# Sheet3.net
KiCad netlist of a schematic drawn in Altium Designer
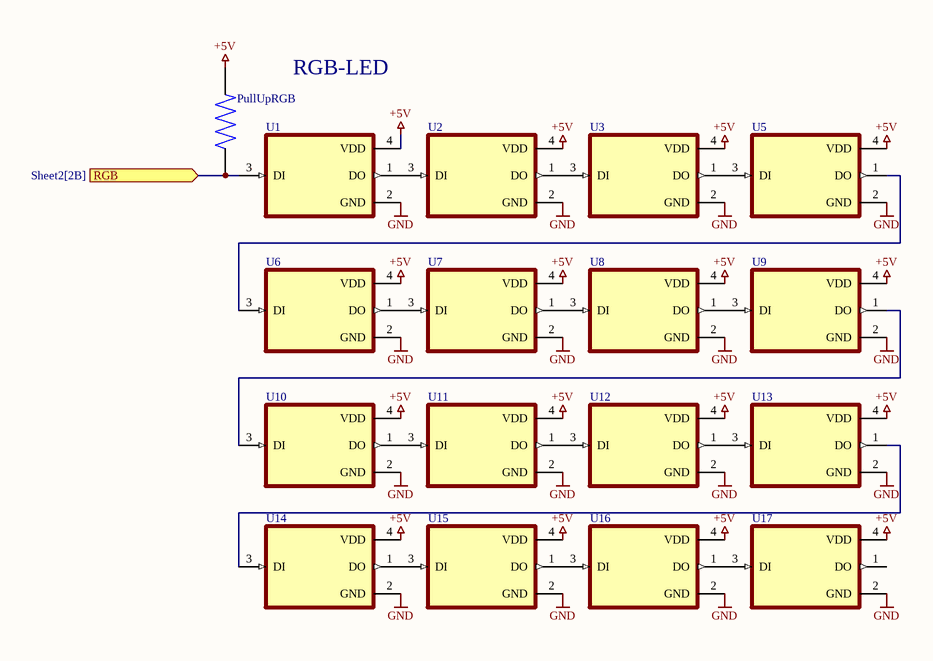
[diagram p0: Sheet3.SchDoc]

(export (version "E")
  (design (tool "Eeschema 10.0.6"))
  (components
    (comp (ref "PullUpRGB")
      (value "CRG0402F4K7")
      (footprint "CRG0402F4K7:RESC1005X40N")
      (fields (field (name "MF") "TE Connectivity") (field (name "TOLERANCE") "1%"))
      (libsource (lib "*") (part "CRG0402F4K7"))
    )
    (comp (ref "U1")
      (value "WS2812-2020")
      (footprint "WS2812_2020:LED_WS2812-2020")
      (description "Intelligent control LED light source, SMD-4")
      (fields (field (name "MF") "Worldsemi"))
      (libsource (lib "*") (part "WS2812-2020"))
    )
    (comp (ref "U2")
      (value "WS2812-2020")
      (footprint "WS2812_2020:LED_WS2812-2020")
      (description "Intelligent control LED light source, SMD-4")
      (fields (field (name "MF") "Worldsemi"))
      (libsource (lib "*") (part "WS2812-2020"))
    )
    (comp (ref "U3")
      (value "WS2812-2020")
      (footprint "WS2812_2020:LED_WS2812-2020")
      (description "Intelligent control LED light source, SMD-4")
      (fields (field (name "MF") "Worldsemi"))
      (libsource (lib "*") (part "WS2812-2020"))
    )
    (comp (ref "U5")
      (value "WS2812-2020")
      (footprint "WS2812_2020:LED_WS2812-2020")
      (description "Intelligent control LED light source, SMD-4")
      (fields (field (name "MF") "Worldsemi"))
      (libsource (lib "*") (part "WS2812-2020"))
    )
    (comp (ref "U6")
      (value "WS2812-2020")
      (footprint "WS2812_2020:LED_WS2812-2020")
      (description "Intelligent control LED light source, SMD-4")
      (fields (field (name "MF") "Worldsemi"))
      (libsource (lib "*") (part "WS2812-2020"))
    )
    (comp (ref "U7")
      (value "WS2812-2020")
      (footprint "WS2812_2020:LED_WS2812-2020")
      (description "Intelligent control LED light source, SMD-4")
      (fields (field (name "MF") "Worldsemi"))
      (libsource (lib "*") (part "WS2812-2020"))
    )
    (comp (ref "U8")
      (value "WS2812-2020")
      (footprint "WS2812_2020:LED_WS2812-2020")
      (description "Intelligent control LED light source, SMD-4")
      (fields (field (name "MF") "Worldsemi"))
      (libsource (lib "*") (part "WS2812-2020"))
    )
    (comp (ref "U9")
      (value "WS2812-2020")
      (footprint "WS2812_2020:LED_WS2812-2020")
      (description "Intelligent control LED light source, SMD-4")
      (fields (field (name "MF") "Worldsemi"))
      (libsource (lib "*") (part "WS2812-2020"))
    )
    (comp (ref "U10")
      (value "WS2812-2020")
      (footprint "WS2812_2020:LED_WS2812-2020")
      (description "Intelligent control LED light source, SMD-4")
      (fields (field (name "MF") "Worldsemi"))
      (libsource (lib "*") (part "WS2812-2020"))
    )
    (comp (ref "U11")
      (value "WS2812-2020")
      (footprint "WS2812_2020:LED_WS2812-2020")
      (description "Intelligent control LED light source, SMD-4")
      (fields (field (name "MF") "Worldsemi"))
      (libsource (lib "*") (part "WS2812-2020"))
    )
    (comp (ref "U12")
      (value "WS2812-2020")
      (footprint "WS2812_2020:LED_WS2812-2020")
      (description "Intelligent control LED light source, SMD-4")
      (fields (field (name "MF") "Worldsemi"))
      (libsource (lib "*") (part "WS2812-2020"))
    )
    (comp (ref "U13")
      (value "WS2812-2020")
      (footprint "WS2812_2020:LED_WS2812-2020")
      (description "Intelligent control LED light source, SMD-4")
      (fields (field (name "MF") "Worldsemi"))
      (libsource (lib "*") (part "WS2812-2020"))
    )
    (comp (ref "U14")
      (value "WS2812-2020")
      (footprint "WS2812_2020:LED_WS2812-2020")
      (description "Intelligent control LED light source, SMD-4")
      (fields (field (name "MF") "Worldsemi"))
      (libsource (lib "*") (part "WS2812-2020"))
    )
    (comp (ref "U15")
      (value "WS2812-2020")
      (footprint "WS2812_2020:LED_WS2812-2020")
      (description "Intelligent control LED light source, SMD-4")
      (fields (field (name "MF") "Worldsemi"))
      (libsource (lib "*") (part "WS2812-2020"))
    )
    (comp (ref "U16")
      (value "WS2812-2020")
      (footprint "WS2812_2020:LED_WS2812-2020")
      (description "Intelligent control LED light source, SMD-4")
      (fields (field (name "MF") "Worldsemi"))
      (libsource (lib "*") (part "WS2812-2020"))
    )
    (comp (ref "U17")
      (value "WS2812-2020")
      (footprint "WS2812_2020:LED_WS2812-2020")
      (description "Intelligent control LED light source, SMD-4")
      (fields (field (name "MF") "Worldsemi"))
      (libsource (lib "*") (part "WS2812-2020"))
    )
  )
  (nets
    (net (code "1") (name "+5V") (class "Default")
      (node (ref "PullUpRGB") (pin "2") (pinfunction "2_2") (pintype "passive"))
      (node (ref "U1") (pin "4") (pinfunction "VDD_4") (pintype "power_in"))
      (node (ref "U10") (pin "4") (pinfunction "VDD_4") (pintype "power_in"))
      (node (ref "U11") (pin "4") (pinfunction "VDD_4") (pintype "power_in"))
      (node (ref "U12") (pin "4") (pinfunction "VDD_4") (pintype "power_in"))
      (node (ref "U13") (pin "4") (pinfunction "VDD_4") (pintype "power_in"))
      (node (ref "U14") (pin "4") (pinfunction "VDD_4") (pintype "power_in"))
      (node (ref "U15") (pin "4") (pinfunction "VDD_4") (pintype "power_in"))
      (node (ref "U16") (pin "4") (pinfunction "VDD_4") (pintype "power_in"))
      (node (ref "U17") (pin "4") (pinfunction "VDD_4") (pintype "power_in"))
      (node (ref "U2") (pin "4") (pinfunction "VDD_4") (pintype "power_in"))
      (node (ref "U3") (pin "4") (pinfunction "VDD_4") (pintype "power_in"))
      (node (ref "U5") (pin "4") (pinfunction "VDD_4") (pintype "power_in"))
      (node (ref "U6") (pin "4") (pinfunction "VDD_4") (pintype "power_in"))
      (node (ref "U7") (pin "4") (pinfunction "VDD_4") (pintype "power_in"))
      (node (ref "U8") (pin "4") (pinfunction "VDD_4") (pintype "power_in"))
      (node (ref "U9") (pin "4") (pinfunction "VDD_4") (pintype "power_in"))
    )
    (net (code "2") (name "/RGB") (class "Default")
      (node (ref "PullUpRGB") (pin "1") (pinfunction "1_1") (pintype "passive"))
      (node (ref "U1") (pin "3") (pinfunction "DI_3") (pintype "input"))
    )
    (net (code "3") (name "GND") (class "Default")
      (node (ref "U1") (pin "2") (pinfunction "GND_2") (pintype "power_in"))
      (node (ref "U10") (pin "2") (pinfunction "GND_2") (pintype "power_in"))
      (node (ref "U11") (pin "2") (pinfunction "GND_2") (pintype "power_in"))
      (node (ref "U12") (pin "2") (pinfunction "GND_2") (pintype "power_in"))
      (node (ref "U13") (pin "2") (pinfunction "GND_2") (pintype "power_in"))
      (node (ref "U14") (pin "2") (pinfunction "GND_2") (pintype "power_in"))
      (node (ref "U15") (pin "2") (pinfunction "GND_2") (pintype "power_in"))
      (node (ref "U16") (pin "2") (pinfunction "GND_2") (pintype "power_in"))
      (node (ref "U17") (pin "2") (pinfunction "GND_2") (pintype "power_in"))
      (node (ref "U2") (pin "2") (pinfunction "GND_2") (pintype "power_in"))
      (node (ref "U3") (pin "2") (pinfunction "GND_2") (pintype "power_in"))
      (node (ref "U5") (pin "2") (pinfunction "GND_2") (pintype "power_in"))
      (node (ref "U6") (pin "2") (pinfunction "GND_2") (pintype "power_in"))
      (node (ref "U7") (pin "2") (pinfunction "GND_2") (pintype "power_in"))
      (node (ref "U8") (pin "2") (pinfunction "GND_2") (pintype "power_in"))
      (node (ref "U9") (pin "2") (pinfunction "GND_2") (pintype "power_in"))
    )
    (net (code "4") (name "Net-(U1-DO)") (class "Default")
      (node (ref "U1") (pin "1") (pinfunction "DO_1") (pintype "output"))
      (node (ref "U2") (pin "3") (pinfunction "DI_3") (pintype "input"))
    )
    (net (code "5") (name "Net-(U2-DO)") (class "Default")
      (node (ref "U2") (pin "1") (pinfunction "DO_1") (pintype "output"))
      (node (ref "U3") (pin "3") (pinfunction "DI_3") (pintype "input"))
    )
    (net (code "6") (name "Net-(U3-DO)") (class "Default")
      (node (ref "U3") (pin "1") (pinfunction "DO_1") (pintype "output"))
      (node (ref "U5") (pin "3") (pinfunction "DI_3") (pintype "input"))
    )
    (net (code "7") (name "Net-(U5-DO)") (class "Default")
      (node (ref "U5") (pin "1") (pinfunction "DO_1") (pintype "output"))
      (node (ref "U6") (pin "3") (pinfunction "DI_3") (pintype "input"))
    )
    (net (code "8") (name "Net-(U6-DO)") (class "Default")
      (node (ref "U6") (pin "1") (pinfunction "DO_1") (pintype "output"))
      (node (ref "U7") (pin "3") (pinfunction "DI_3") (pintype "input"))
    )
    (net (code "9") (name "Net-(U7-DO)") (class "Default")
      (node (ref "U7") (pin "1") (pinfunction "DO_1") (pintype "output"))
      (node (ref "U8") (pin "3") (pinfunction "DI_3") (pintype "input"))
    )
    (net (code "10") (name "Net-(U8-DO)") (class "Default")
      (node (ref "U8") (pin "1") (pinfunction "DO_1") (pintype "output"))
      (node (ref "U9") (pin "3") (pinfunction "DI_3") (pintype "input"))
    )
    (net (code "11") (name "Net-(U10-DI)") (class "Default")
      (node (ref "U10") (pin "3") (pinfunction "DI_3") (pintype "input"))
      (node (ref "U9") (pin "1") (pinfunction "DO_1") (pintype "output"))
    )
    (net (code "12") (name "Net-(U10-DO)") (class "Default")
      (node (ref "U10") (pin "1") (pinfunction "DO_1") (pintype "output"))
      (node (ref "U11") (pin "3") (pinfunction "DI_3") (pintype "input"))
    )
    (net (code "13") (name "Net-(U11-DO)") (class "Default")
      (node (ref "U11") (pin "1") (pinfunction "DO_1") (pintype "output"))
      (node (ref "U12") (pin "3") (pinfunction "DI_3") (pintype "input"))
    )
    (net (code "14") (name "Net-(U12-DO)") (class "Default")
      (node (ref "U12") (pin "1") (pinfunction "DO_1") (pintype "output"))
      (node (ref "U13") (pin "3") (pinfunction "DI_3") (pintype "input"))
    )
    (net (code "15") (name "Net-(U13-DO)") (class "Default")
      (node (ref "U13") (pin "1") (pinfunction "DO_1") (pintype "output"))
      (node (ref "U14") (pin "3") (pinfunction "DI_3") (pintype "input"))
    )
    (net (code "16") (name "Net-(U14-DO)") (class "Default")
      (node (ref "U14") (pin "1") (pinfunction "DO_1") (pintype "output"))
      (node (ref "U15") (pin "3") (pinfunction "DI_3") (pintype "input"))
    )
    (net (code "17") (name "Net-(U15-DO)") (class "Default")
      (node (ref "U15") (pin "1") (pinfunction "DO_1") (pintype "output"))
      (node (ref "U16") (pin "3") (pinfunction "DI_3") (pintype "input"))
    )
    (net (code "18") (name "Net-(U16-DO)") (class "Default")
      (node (ref "U16") (pin "1") (pinfunction "DO_1") (pintype "output"))
      (node (ref "U17") (pin "3") (pinfunction "DI_3") (pintype "input"))
    )
    (net (code "19") (name "unconnected-(U17-DO-Pad1)") (class "Default")
      (node (ref "U17") (pin "1") (pinfunction "DO_1") (pintype "output"))
    )
  )
)
